# module_using_8266.net
KiCad netlist of a schematic drawn in Altium Designer
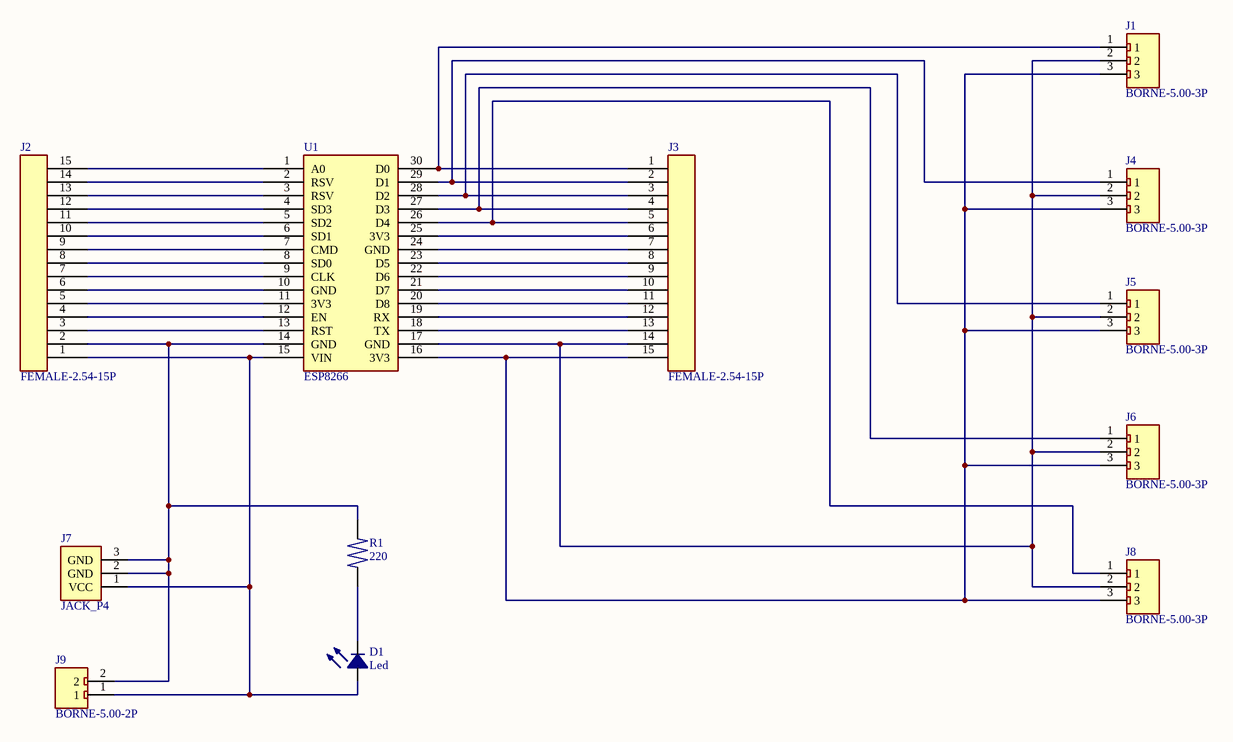
[diagram p0: module_using_8266.SchDoc]

(export (version "E")
  (design (tool "Eeschema 10.0.6"))
  (components
    (comp (ref "D1")
      (value "Led")
      (footprint "LED_5mm_BLUE")
      (description "LED PTH 5mm Blue.")
      (libsource (lib "LED") (part "LED_5mm_BLUE"))
    )
    (comp (ref "J1")
      (value "BORNE-5.00-3P")
      (footprint "BORNE-5.00-3P")
      (description "Borne 3 Vias, Pitch 5mm.")
      (libsource (lib "Connectors") (part "BORNE-5.00-3P"))
    )
    (comp (ref "J2")
      (value "FEMALE-2.54-15P")
      (footprint "FEMALE-2.54-15P")
      (description "Female Header Connector 2.54mm 15 Pins.")
      (libsource (lib "") (part "FEMALE-2.54-15P_1"))
    )
    (comp (ref "J3")
      (value "FEMALE-2.54-15P")
      (footprint "FEMALE-2.54-15P")
      (description "Female Header Connector 2.54mm 15 Pins.")
      (libsource (lib "Connectors") (part "FEMALE-2.54-15P"))
    )
    (comp (ref "J4")
      (value "BORNE-5.00-3P")
      (footprint "BORNE-5.00-3P")
      (description "Borne 3 Vias, Pitch 5mm.")
      (libsource (lib "Connectors") (part "BORNE-5.00-3P"))
    )
    (comp (ref "J5")
      (value "BORNE-5.00-3P")
      (footprint "BORNE-5.00-3P")
      (description "Borne 3 Vias, Pitch 5mm.")
      (libsource (lib "Connectors") (part "BORNE-5.00-3P"))
    )
    (comp (ref "J6")
      (value "BORNE-5.00-3P")
      (footprint "BORNE-5.00-3P")
      (description "Borne 3 Vias, Pitch 5mm.")
      (libsource (lib "Connectors") (part "BORNE-5.00-3P"))
    )
    (comp (ref "J7")
      (value "JACK_P4")
      (footprint "JACK_P4")
      (description "9V Battery Connector Jack P4.")
      (libsource (lib "Connectors") (part "JACK_P4"))
    )
    (comp (ref "J8")
      (value "BORNE-5.00-3P")
      (footprint "BORNE-5.00-3P")
      (description "Borne 3 Vias, Pitch 5mm.")
      (libsource (lib "Connectors") (part "BORNE-5.00-3P"))
    )
    (comp (ref "J9")
      (value "BORNE-5.00-2P")
      (footprint "BORNE-5.00-2P")
      (description "Borne 2 Vias, Pitch 5mm.")
      (libsource (lib "Connectors") (part "BORNE-5.00-2P"))
    )
    (comp (ref "R1")
      (value "220")
      (footprint "RESISTOR_PTH_9.5mm")
      (description "Generic Resistor 9.5mm.")
      (libsource (lib "Resistors") (part "RESISTOR_9.5mm"))
    )
    (comp (ref "U1")
      (value "ESP8266")
      (footprint "ESP8266")
      (description "Microcontoller Board 30 Pins Wifi 2.4GHz BLE 4.2 ESP-12F")
      (libsource (lib "Espressif Microcontrollers") (part "ESP8266"))
    )
  )
  (nets
    (net (code "1") (name "Net-(D1-Pad2)") (class "Default")
      (node (ref "D1") (pin "2") (pinfunction "2_2") (pintype "passive"))
      (node (ref "R1") (pin "1") (pinfunction "1_1") (pintype "passive"))
    )
    (net (code "2") (name "Net-(J1-Pad2)") (class "Default")
      (node (ref "J1") (pin "2") (pinfunction "2_2") (pintype "passive"))
      (node (ref "J3") (pin "14") (pintype "passive"))
      (node (ref "J4") (pin "2") (pinfunction "2_2") (pintype "passive"))
      (node (ref "J5") (pin "2") (pinfunction "2_2") (pintype "passive"))
      (node (ref "J6") (pin "2") (pinfunction "2_2") (pintype "passive"))
      (node (ref "J8") (pin "2") (pinfunction "2_2") (pintype "passive"))
      (node (ref "U1") (pin "17") (pinfunction "GND_17") (pintype "passive"))
    )
    (net (code "3") (name "Net-(J1-Pad3)") (class "Default")
      (node (ref "J1") (pin "3") (pinfunction "3_3") (pintype "passive"))
      (node (ref "J3") (pin "15") (pintype "passive"))
      (node (ref "J4") (pin "3") (pinfunction "3_3") (pintype "passive"))
      (node (ref "J5") (pin "3") (pinfunction "3_3") (pintype "passive"))
      (node (ref "J6") (pin "3") (pinfunction "3_3") (pintype "passive"))
      (node (ref "J8") (pin "3") (pinfunction "3_3") (pintype "passive"))
      (node (ref "U1") (pin "16") (pinfunction "3V3_16") (pintype "passive"))
    )
    (net (code "4") (name "Net-(J2-Pad2)") (class "Default")
      (node (ref "J2") (pin "2") (pintype "passive"))
      (node (ref "J7") (pin "2") (pinfunction "GND_2") (pintype "passive"))
      (node (ref "J7") (pin "3") (pinfunction "GND_3") (pintype "passive"))
      (node (ref "J9") (pin "2") (pinfunction "2_2") (pintype "passive"))
      (node (ref "R1") (pin "2") (pinfunction "2_2") (pintype "passive"))
      (node (ref "U1") (pin "14") (pinfunction "GND_14") (pintype "passive"))
    )
    (net (code "5") (name "Net-(J2-Pad5)") (class "Default")
      (node (ref "J2") (pin "5") (pintype "passive"))
      (node (ref "U1") (pin "11") (pinfunction "3V3_11") (pintype "passive"))
    )
    (net (code "6") (name "Net-(J2-Pad6)") (class "Default")
      (node (ref "J2") (pin "6") (pintype "passive"))
      (node (ref "U1") (pin "10") (pinfunction "GND_10") (pintype "passive"))
    )
    (net (code "7") (name "Net-(J2-Pad13)") (class "Default")
      (node (ref "J2") (pin "13") (pintype "passive"))
      (node (ref "U1") (pin "3") (pinfunction "RSV_3") (pintype "passive"))
    )
    (net (code "8") (name "Net-(J2-Pad14)") (class "Default")
      (node (ref "J2") (pin "14") (pintype "passive"))
      (node (ref "U1") (pin "2") (pinfunction "RSV_2") (pintype "passive"))
    )
    (net (code "9") (name "Net-(J3-Pad6)") (class "Default")
      (node (ref "J3") (pin "6") (pintype "passive"))
      (node (ref "U1") (pin "25") (pinfunction "3V3_25") (pintype "passive"))
    )
    (net (code "10") (name "Net-(J3-Pad7)") (class "Default")
      (node (ref "J3") (pin "7") (pintype "passive"))
      (node (ref "U1") (pin "24") (pinfunction "GND_24") (pintype "passive"))
    )
    (net (code "11") (name "Net-(J7-VCC)") (class "Default")
      (node (ref "D1") (pin "1") (pinfunction "1_1") (pintype "passive"))
      (node (ref "J2") (pin "1") (pintype "passive"))
      (node (ref "J7") (pin "1") (pinfunction "VCC_1") (pintype "passive"))
      (node (ref "J9") (pin "1") (pinfunction "1_1") (pintype "passive"))
      (node (ref "U1") (pin "15") (pinfunction "VIN_15") (pintype "passive"))
    )
    (net (code "12") (name "Net-(U1-A0)") (class "Default")
      (node (ref "J2") (pin "15") (pintype "passive"))
      (node (ref "U1") (pin "1") (pinfunction "A0_1") (pintype "passive"))
    )
    (net (code "13") (name "Net-(U1-CLK)") (class "Default")
      (node (ref "J2") (pin "7") (pintype "passive"))
      (node (ref "U1") (pin "9") (pinfunction "CLK_9") (pintype "passive"))
    )
    (net (code "14") (name "Net-(U1-CMD)") (class "Default")
      (node (ref "J2") (pin "9") (pintype "passive"))
      (node (ref "U1") (pin "7") (pinfunction "CMD_7") (pintype "passive"))
    )
    (net (code "15") (name "Net-(U1-D0)") (class "Default")
      (node (ref "J1") (pin "1") (pinfunction "1_1") (pintype "passive"))
      (node (ref "J3") (pin "1") (pintype "passive"))
      (node (ref "U1") (pin "30") (pinfunction "D0_30") (pintype "passive"))
    )
    (net (code "16") (name "Net-(U1-D1)") (class "Default")
      (node (ref "J3") (pin "2") (pintype "passive"))
      (node (ref "J4") (pin "1") (pinfunction "1_1") (pintype "passive"))
      (node (ref "U1") (pin "29") (pinfunction "D1_29") (pintype "passive"))
    )
    (net (code "17") (name "Net-(U1-D2)") (class "Default")
      (node (ref "J3") (pin "3") (pintype "passive"))
      (node (ref "J5") (pin "1") (pinfunction "1_1") (pintype "passive"))
      (node (ref "U1") (pin "28") (pinfunction "D2_28") (pintype "passive"))
    )
    (net (code "18") (name "Net-(U1-D3)") (class "Default")
      (node (ref "J3") (pin "4") (pintype "passive"))
      (node (ref "J6") (pin "1") (pinfunction "1_1") (pintype "passive"))
      (node (ref "U1") (pin "27") (pinfunction "D3_27") (pintype "passive"))
    )
    (net (code "19") (name "Net-(U1-D4)") (class "Default")
      (node (ref "J3") (pin "5") (pintype "passive"))
      (node (ref "J8") (pin "1") (pinfunction "1_1") (pintype "passive"))
      (node (ref "U1") (pin "26") (pinfunction "D4_26") (pintype "passive"))
    )
    (net (code "20") (name "Net-(U1-D5)") (class "Default")
      (node (ref "J3") (pin "8") (pintype "passive"))
      (node (ref "U1") (pin "23") (pinfunction "D5_23") (pintype "passive"))
    )
    (net (code "21") (name "Net-(U1-D6)") (class "Default")
      (node (ref "J3") (pin "9") (pintype "passive"))
      (node (ref "U1") (pin "22") (pinfunction "D6_22") (pintype "passive"))
    )
    (net (code "22") (name "Net-(U1-D7)") (class "Default")
      (node (ref "J3") (pin "10") (pintype "passive"))
      (node (ref "U1") (pin "21") (pinfunction "D7_21") (pintype "passive"))
    )
    (net (code "23") (name "Net-(U1-D8)") (class "Default")
      (node (ref "J3") (pin "11") (pintype "passive"))
      (node (ref "U1") (pin "20") (pinfunction "D8_20") (pintype "passive"))
    )
    (net (code "24") (name "Net-(U1-EN)") (class "Default")
      (node (ref "J2") (pin "4") (pintype "passive"))
      (node (ref "U1") (pin "12") (pinfunction "EN_12") (pintype "passive"))
    )
    (net (code "25") (name "Net-(U1-RST)") (class "Default")
      (node (ref "J2") (pin "3") (pintype "passive"))
      (node (ref "U1") (pin "13") (pinfunction "RST_13") (pintype "passive"))
    )
    (net (code "26") (name "Net-(U1-RX)") (class "Default")
      (node (ref "J3") (pin "12") (pintype "passive"))
      (node (ref "U1") (pin "19") (pinfunction "RX_19") (pintype "passive"))
    )
    (net (code "27") (name "Net-(U1-SD0)") (class "Default")
      (node (ref "J2") (pin "8") (pintype "passive"))
      (node (ref "U1") (pin "8") (pinfunction "SD0_8") (pintype "passive"))
    )
    (net (code "28") (name "Net-(U1-SD1)") (class "Default")
      (node (ref "J2") (pin "10") (pintype "passive"))
      (node (ref "U1") (pin "6") (pinfunction "SD1_6") (pintype "passive"))
    )
    (net (code "29") (name "Net-(U1-SD2)") (class "Default")
      (node (ref "J2") (pin "11") (pintype "passive"))
      (node (ref "U1") (pin "5") (pinfunction "SD2_5") (pintype "passive"))
    )
    (net (code "30") (name "Net-(U1-SD3)") (class "Default")
      (node (ref "J2") (pin "12") (pintype "passive"))
      (node (ref "U1") (pin "4") (pinfunction "SD3_4") (pintype "passive"))
    )
    (net (code "31") (name "Net-(U1-TX)") (class "Default")
      (node (ref "J3") (pin "13") (pintype "passive"))
      (node (ref "U1") (pin "18") (pinfunction "TX_18") (pintype "passive"))
    )
  )
)
